# NRF_Schematic.net
KiCad netlist of a schematic drawn in Altium Designer
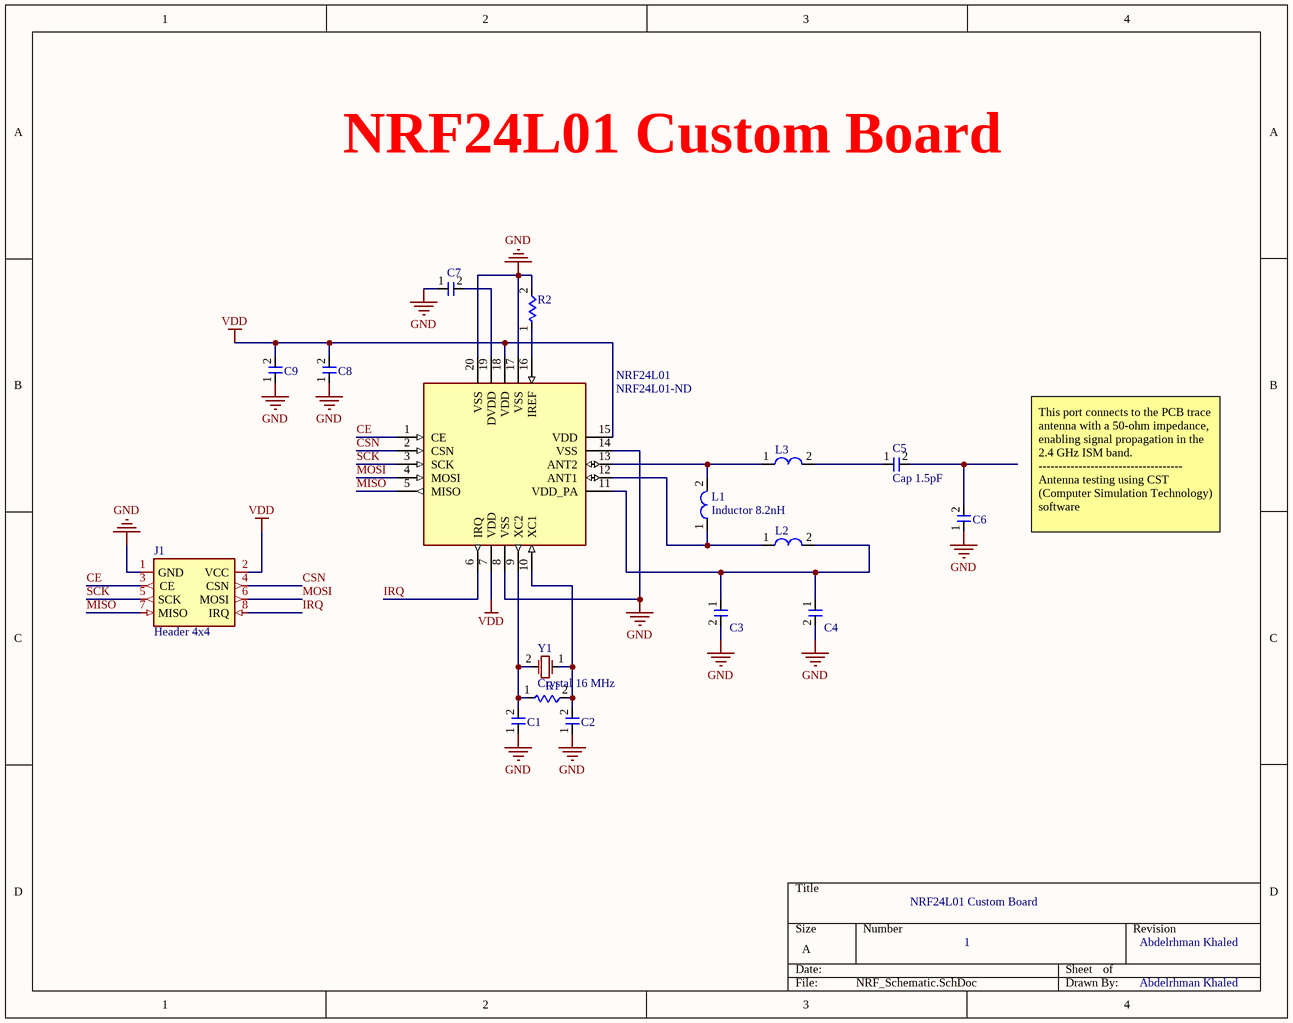
[diagram p0: NRF_Schematic.SchDoc]

(export (version "E")
  (design (tool "Eeschema 10.0.6"))
  (components
    (comp (ref "C1")
      (value "Cap 22pF")
      (footprint "Cap 22pF")
      (libsource (lib "NRF24L01_Integrated_Library") (part "Cap 22pF"))
    )
    (comp (ref "C2")
      (value "Cap 22pF")
      (footprint "Cap 22pF")
      (libsource (lib "NRF24L01_Integrated_Library") (part "Cap 22pF"))
    )
    (comp (ref "C3")
      (value "Cap 2.2nF")
      (footprint "Cap 2.2nF")
      (libsource (lib "NRF24L01_Integrated_Library") (part "Cap 2.2nF"))
    )
    (comp (ref "C4")
      (value "Cap 4.7pF")
      (footprint "Cap 4.7 pF")
      (libsource (lib "NRF24L01_Integrated_Library") (part "Cap 4.7pF"))
    )
    (comp (ref "C5")
      (value "Cap 1.5pF")
      (footprint "Cap 1.5pF")
      (libsource (lib "NRF24L01_Integrated_Library") (part "Cap 1.5pF"))
    )
    (comp (ref "C6")
      (value "Cap 1 pF")
      (footprint "Cap 1pF")
      (libsource (lib "NRF24L01_Integrated_Library") (part "Cap 1 pF"))
    )
    (comp (ref "C7")
      (value "Cap 33nf")
      (footprint "Cap 33nF")
      (libsource (lib "NRF24L01_Integrated_Library") (part "Cap 33nf"))
    )
    (comp (ref "C8")
      (value "Cap 10nF")
      (footprint "Cap 10nF")
      (libsource (lib "NRF24L01_Integrated_Library") (part "Cap 10nF"))
    )
    (comp (ref "C9")
      (value "Cap 10nF")
      (footprint "Cap 10nF")
      (libsource (lib "NRF24L01_Integrated_Library") (part "Cap 10nF"))
    )
    (comp (ref "J1")
      (value "Header 4x4")
      (footprint "Header 4x4")
      (libsource (lib "NRF24L01_Integrated_Library") (part "Header 4x4"))
    )
    (comp (ref "L1")
      (value "Inductor 8.2nH")
      (footprint "Inductor 8.2nH")
      (description "FIXED IND 8.2NH 680MA 100MOHM SM")
      (fields (field (name "PART NUMBER") "AISC-0402-8N2G-T"))
      (libsource (lib "NRF24L01_Integrated_Library") (part "Inductor 8.2nH"))
    )
    (comp (ref "L2")
      (value "Inductor 2.7nH")
      (footprint "Inductor 2.7nH")
      (libsource (lib "NRF24L01_Integrated_Library") (part "Inductor 2.7nH"))
    )
    (comp (ref "L3")
      (value "Inductor 3.9 nH")
      (footprint "Inductor 3.9nH")
      (libsource (lib "NRF24L01_Integrated_Library") (part "Inductor 3.9 nH"))
    )
    (comp (ref "NRF24L01")
      (value "NRF24L01-ND")
      (footprint "NRF24L01-ND")
      (description "IC RF TxRx Only General ISM > 1GHz 2.4GHz 20-VFQFN Exposed Pad")
      (libsource (lib "NRF24L01_Integrated_Library") (part "NRF24L01-ND"))
    )
    (comp (ref "R1")
      (value "Resistance 1M Ohm")
      (footprint "Resistor 1 M Ohm")
      (libsource (lib "NRF24L01_Integrated_Library") (part "Resistance 1M Ohm"))
    )
    (comp (ref "R2")
      (value "Resistance 22k Ohm")
      (footprint "Resistor 22k Ohm")
      (libsource (lib "NRF24L01_Integrated_Library") (part "Resistance 22k Ohm"))
    )
    (comp (ref "Y1")
      (value "Crystal 16 MHz")
      (footprint "Crystal 16MHz")
      (description "CRYSTAL 4.0000MHZ 12PF SMD")
      (fields (field (name "PART NUMBER") "J49SMH-A-G-G-K-4M0"))
      (libsource (lib "NRF24L01_Integrated_Library") (part "Crystal 16 MHz"))
    )
  )
  (nets
    (net (code "1") (name "/CE") (class "Default")
      (node (ref "J1") (pin "3") (pinfunction "CE_3") (pintype "output"))
      (node (ref "NRF24L01") (pin "1") (pinfunction "CE_1") (pintype "input"))
    )
    (net (code "2") (name "/CSN") (class "Default")
      (node (ref "J1") (pin "4") (pinfunction "CSN_4") (pintype "output"))
      (node (ref "NRF24L01") (pin "2") (pinfunction "CSN_2") (pintype "input"))
    )
    (net (code "3") (name "/IRQ") (class "Default")
      (node (ref "J1") (pin "8") (pinfunction "IRQ_8") (pintype "input"))
      (node (ref "NRF24L01") (pin "6") (pinfunction "IRQ_6") (pintype "output"))
    )
    (net (code "4") (name "/MISO") (class "Default")
      (node (ref "J1") (pin "7") (pinfunction "MISO_7") (pintype "input"))
      (node (ref "NRF24L01") (pin "5") (pinfunction "MISO_5") (pintype "output"))
    )
    (net (code "5") (name "/MOSI") (class "Default")
      (node (ref "J1") (pin "6") (pinfunction "MOSI_6") (pintype "output"))
      (node (ref "NRF24L01") (pin "4") (pinfunction "MOSI_4") (pintype "input"))
    )
    (net (code "6") (name "/SCK") (class "Default")
      (node (ref "J1") (pin "5") (pinfunction "SCK_5") (pintype "output"))
      (node (ref "NRF24L01") (pin "3") (pinfunction "SCK_3") (pintype "input"))
    )
    (net (code "7") (name "GND") (class "Default")
      (node (ref "C1") (pin "1") (pinfunction "Pin_1_1") (pintype "passive"))
      (node (ref "C2") (pin "1") (pinfunction "Pin_1_1") (pintype "passive"))
      (node (ref "C3") (pin "2") (pinfunction "Pin_2_2") (pintype "passive"))
      (node (ref "C4") (pin "2") (pinfunction "Pin_2_2") (pintype "passive"))
      (node (ref "C6") (pin "1") (pinfunction "Pin_1_1") (pintype "passive"))
      (node (ref "C7") (pin "1") (pinfunction "Pin_1_1") (pintype "passive"))
      (node (ref "C8") (pin "1") (pinfunction "Pin_1_1") (pintype "passive"))
      (node (ref "C9") (pin "1") (pinfunction "Pin_1_1") (pintype "passive"))
      (node (ref "J1") (pin "1") (pinfunction "GND_1") (pintype "power_in"))
      (node (ref "NRF24L01") (pin "14") (pinfunction "VSS_14") (pintype "power_in"))
      (node (ref "NRF24L01") (pin "17") (pinfunction "VSS_17") (pintype "power_in"))
      (node (ref "NRF24L01") (pin "20") (pinfunction "VSS_20") (pintype "power_in"))
      (node (ref "NRF24L01") (pin "8") (pinfunction "VSS_8") (pintype "power_in"))
      (node (ref "R2") (pin "2") (pinfunction "pin_2_2") (pintype "passive"))
    )
    (net (code "8") (name "Net-(C1-Pin_2)") (class "Default")
      (node (ref "C1") (pin "2") (pinfunction "Pin_2_2") (pintype "passive"))
      (node (ref "NRF24L01") (pin "9") (pinfunction "XC2_9") (pintype "output"))
      (node (ref "R1") (pin "1") (pinfunction "Pin_1_1") (pintype "passive"))
      (node (ref "Y1") (pin "2") (pinfunction "3_2") (pintype "passive"))
    )
    (net (code "9") (name "Net-(C2-Pin_2)") (class "Default")
      (node (ref "C2") (pin "2") (pinfunction "Pin_2_2") (pintype "passive"))
      (node (ref "NRF24L01") (pin "10") (pinfunction "XC1_10") (pintype "input"))
      (node (ref "R1") (pin "2") (pinfunction "pin_2_2") (pintype "passive"))
      (node (ref "Y1") (pin "1") (pinfunction "3_1") (pintype "passive"))
    )
    (net (code "10") (name "Net-(C3-Pin_1)") (class "Default")
      (node (ref "C3") (pin "1") (pinfunction "Pin_1_1") (pintype "passive"))
      (node (ref "C4") (pin "1") (pinfunction "Pin_1_1") (pintype "passive"))
      (node (ref "L2") (pin "2") (pinfunction "11_2") (pintype "passive"))
      (node (ref "NRF24L01") (pin "11") (pinfunction "VDD_PA_11") (pintype "power_in"))
    )
    (net (code "11") (name "Net-(C5-Pin_1)") (class "Default")
      (node (ref "C5") (pin "1") (pinfunction "Pin_1_1") (pintype "passive"))
      (node (ref "L3") (pin "2") (pinfunction "11_2") (pintype "passive"))
    )
    (net (code "12") (name "Net-(C5-Pin_2)") (class "Default")
      (node (ref "C5") (pin "2") (pinfunction "Pin_2_2") (pintype "passive"))
      (node (ref "C6") (pin "2") (pinfunction "Pin_2_2") (pintype "passive"))
    )
    (net (code "13") (name "Net-(C7-Pin_2)") (class "Default")
      (node (ref "C7") (pin "2") (pinfunction "Pin_2_2") (pintype "passive"))
      (node (ref "NRF24L01") (pin "19") (pinfunction "DVDD_19") (pintype "power_in"))
    )
    (net (code "14") (name "Net-(NRF24L01-ANT1)") (class "Default")
      (node (ref "L1") (pin "1") (pinfunction "11_1") (pintype "passive"))
      (node (ref "L2") (pin "1") (pinfunction "11_1") (pintype "passive"))
      (node (ref "NRF24L01") (pin "12") (pinfunction "ANT1_12") (pintype "bidirectional"))
    )
    (net (code "15") (name "Net-(NRF24L01-ANT2)") (class "Default")
      (node (ref "L1") (pin "2") (pinfunction "11_2") (pintype "passive"))
      (node (ref "L3") (pin "1") (pinfunction "11_1") (pintype "passive"))
      (node (ref "NRF24L01") (pin "13") (pinfunction "ANT2_13") (pintype "bidirectional"))
    )
    (net (code "16") (name "Net-(NRF24L01-IREF)") (class "Default")
      (node (ref "NRF24L01") (pin "16") (pinfunction "IREF_16") (pintype "input"))
      (node (ref "R2") (pin "1") (pinfunction "Pin_1_1") (pintype "passive"))
    )
    (net (code "17") (name "VDD") (class "Default")
      (node (ref "C8") (pin "2") (pinfunction "Pin_2_2") (pintype "passive"))
      (node (ref "C9") (pin "2") (pinfunction "Pin_2_2") (pintype "passive"))
      (node (ref "J1") (pin "2") (pinfunction "VCC_2") (pintype "power_in"))
      (node (ref "NRF24L01") (pin "15") (pinfunction "VDD_15") (pintype "power_in"))
      (node (ref "NRF24L01") (pin "18") (pinfunction "VDD_18") (pintype "power_in"))
      (node (ref "NRF24L01") (pin "7") (pinfunction "VDD_7") (pintype "power_in"))
    )
  )
)
